# ETAPA_DE_POTENCIA.net
KiCad netlist of a schematic drawn in Altium Designer
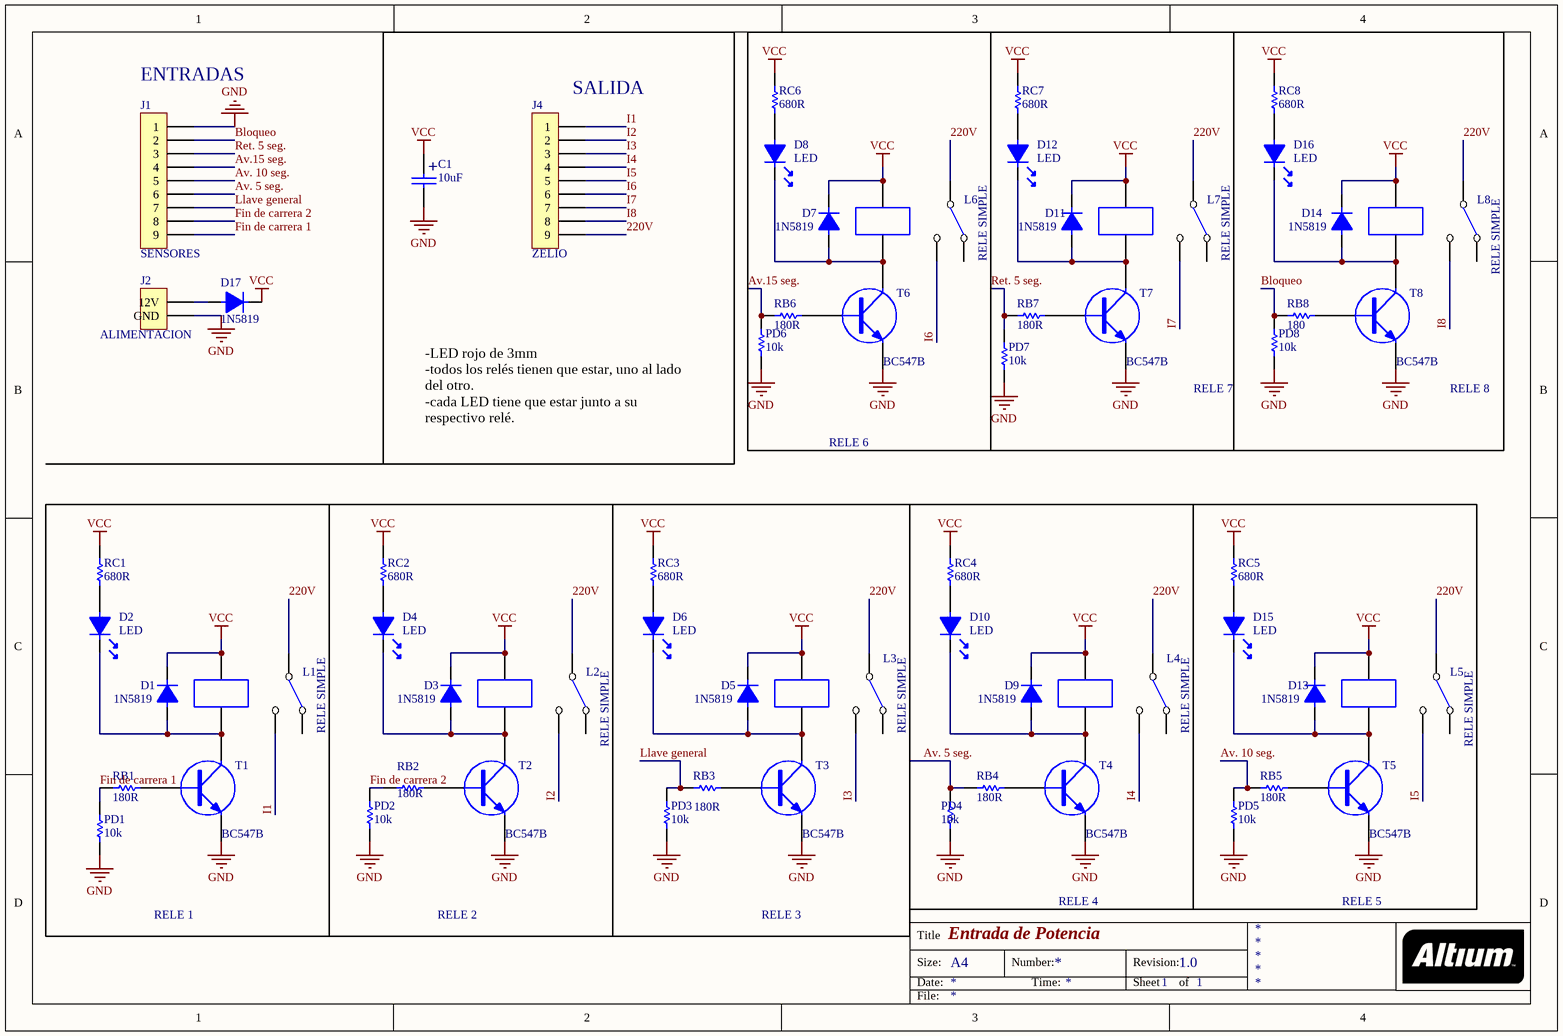
[diagram p0: ETAPA DE POTENCIA (1).SchDoc]

(export (version "E")
  (design (tool "Eeschema 10.0.6"))
  (components
    (comp (ref "C1") (value "10uF") (footprint "CAP100RP") (libsource (lib "LIBEBAL") (part "CAPPOL")))
    (comp (ref "D1") (value "1N5819") (footprint "DO41") (libsource (lib "LIBEBAL") (part "DIODO")))
    (comp (ref "D2") (value "LED") (footprint "LED3") (libsource (lib "LIBEBAL") (part "LED")))
    (comp (ref "D3") (value "1N5819") (footprint "DO41") (libsource (lib "LIBEBAL") (part "DIODO")))
    (comp (ref "D4") (value "LED") (footprint "LED3") (libsource (lib "LIBEBAL") (part "LED")))
    (comp (ref "D5") (value "1N5819") (footprint "DO41") (libsource (lib "LIBEBAL") (part "DIODO")))
    (comp (ref "D6") (value "LED") (footprint "LED3") (libsource (lib "LIBEBAL") (part "LED")))
    (comp (ref "D7") (value "1N5819") (footprint "DO41") (libsource (lib "LIBEBAL") (part "DIODO")))
    (comp (ref "D8") (value "LED") (footprint "LED3") (libsource (lib "LIBEBAL") (part "LED")))
    (comp (ref "D9") (value "1N5819") (footprint "DO41") (libsource (lib "LIBEBAL") (part "DIODO")))
    (comp (ref "D10") (value "LED") (footprint "LED3") (libsource (lib "LIBEBAL") (part "LED")))
    (comp (ref "D11") (value "1N5819") (footprint "DO41") (libsource (lib "LIBEBAL") (part "DIODO")))
    (comp (ref "D12") (value "LED") (footprint "LED3") (libsource (lib "LIBEBAL") (part "LED")))
    (comp (ref "D13") (value "1N5819") (footprint "DO41") (libsource (lib "LIBEBAL") (part "DIODO")))
    (comp (ref "D14") (value "1N5819") (footprint "DO41") (libsource (lib "LIBEBAL") (part "DIODO")))
    (comp (ref "D15") (value "LED") (footprint "LED3") (libsource (lib "LIBEBAL") (part "LED")))
    (comp (ref "D16") (value "LED") (footprint "LED3") (libsource (lib "LIBEBAL") (part "LED")))
    (comp (ref "D17") (value "1N5819") (footprint "DO41") (libsource (lib "LIBPIOIX 0314A") (part "DIODO")))
    (comp (ref "J1") (value "SENSORES") (footprint "BORNERA9") (libsource (lib "LIBEBAL") (part "BORNERA 9")))
    (comp (ref "J2")
      (value "ALIMENTACION")
      (footprint "BORNERA2")
      (libsource (lib "LIBEBAL") (part "BORNERA 2"))
    )
    (comp (ref "J4") (value "ZELIO") (footprint "BORNERA9") (libsource (lib "LIBEBAL") (part "BORNERA 9")))
    (comp (ref "L1")
      (value "RELE SIMPLE")
      (footprint "RELE SERIE 964")
      (libsource (lib "LIBEBAL") (part "RELE SIMPLE"))
    )
    (comp (ref "L2")
      (value "RELE SIMPLE")
      (footprint "RELE SERIE 964")
      (libsource (lib "LIBEBAL") (part "RELE SIMPLE"))
    )
    (comp (ref "L3")
      (value "RELE SIMPLE")
      (footprint "RELE SERIE 964")
      (libsource (lib "LIBEBAL") (part "RELE SIMPLE"))
    )
    (comp (ref "L4")
      (value "RELE SIMPLE")
      (footprint "RELE SERIE 964")
      (libsource (lib "LIBEBAL") (part "RELE SIMPLE"))
    )
    (comp (ref "L5")
      (value "RELE SIMPLE")
      (footprint "RELE SERIE 964")
      (libsource (lib "LIBEBAL") (part "RELE SIMPLE"))
    )
    (comp (ref "L6")
      (value "RELE SIMPLE")
      (footprint "RELE SERIE 964")
      (libsource (lib "LIBEBAL") (part "RELE SIMPLE"))
    )
    (comp (ref "L7")
      (value "RELE SIMPLE")
      (footprint "RELE SERIE 964")
      (libsource (lib "LIBEBAL") (part "RELE SIMPLE"))
    )
    (comp (ref "L8")
      (value "RELE SIMPLE")
      (footprint "RELE SERIE 964")
      (libsource (lib "LIBEBAL") (part "RELE SIMPLE"))
    )
    (comp (ref "PD1") (value "10k") (footprint "RES400") (libsource (lib "LIBEBAL") (part "RES")))
    (comp (ref "PD2") (value "10k") (footprint "RES400") (libsource (lib "LIBEBAL") (part "RES")))
    (comp (ref "PD3") (value "10k") (footprint "RES400") (libsource (lib "LIBEBAL") (part "RES")))
    (comp (ref "PD4") (value "10k") (footprint "RES400") (libsource (lib "LIBEBAL") (part "RES")))
    (comp (ref "PD5") (value "10k") (footprint "RES400") (libsource (lib "LIBEBAL") (part "RES")))
    (comp (ref "PD6") (value "10k") (footprint "RES400") (libsource (lib "LIBEBAL") (part "RES")))
    (comp (ref "PD7") (value "10k") (footprint "RES400") (libsource (lib "LIBEBAL") (part "RES")))
    (comp (ref "PD8") (value "10k") (footprint "RES400") (libsource (lib "LIBEBAL") (part "RES")))
    (comp (ref "RB1") (value "180R") (footprint "RES400") (libsource (lib "LIBEBAL") (part "RES")))
    (comp (ref "RB2") (value "180R") (footprint "RES400") (libsource (lib "LIBEBAL") (part "RES")))
    (comp (ref "RB3") (value "180R") (footprint "RES400") (libsource (lib "LIBEBAL") (part "RES")))
    (comp (ref "RB4") (value "180R") (footprint "RES400") (libsource (lib "LIBEBAL") (part "RES")))
    (comp (ref "RB5") (value "180R") (footprint "RES400") (libsource (lib "LIBEBAL") (part "RES")))
    (comp (ref "RB6") (value "180R") (footprint "RES400") (libsource (lib "LIBEBAL") (part "RES")))
    (comp (ref "RB7") (value "180R") (footprint "RES400") (libsource (lib "LIBEBAL") (part "RES")))
    (comp (ref "RB8") (value "180") (footprint "RES400") (libsource (lib "LIBEBAL") (part "RES")))
    (comp (ref "RC1") (value "680R") (footprint "RES400") (libsource (lib "LIBEBAL") (part "RES")))
    (comp (ref "RC2") (value "680R") (footprint "RES400") (libsource (lib "LIBEBAL") (part "RES")))
    (comp (ref "RC3") (value "680R") (footprint "RES400") (libsource (lib "LIBEBAL") (part "RES")))
    (comp (ref "RC4") (value "680R") (footprint "RES400") (libsource (lib "LIBEBAL") (part "RES")))
    (comp (ref "RC5") (value "680R") (footprint "RES400") (libsource (lib "LIBEBAL") (part "RES")))
    (comp (ref "RC6") (value "680R") (footprint "RES400") (libsource (lib "LIBEBAL") (part "RES")))
    (comp (ref "RC7") (value "680R") (footprint "RES400") (libsource (lib "LIBEBAL") (part "RES")))
    (comp (ref "RC8") (value "680R") (footprint "RES400") (libsource (lib "LIBEBAL") (part "RES")))
    (comp (ref "T1") (value "BC547B") (footprint "TO92") (libsource (lib "LIBEBAL") (part "TRANSISTOR NPN")))
    (comp (ref "T2") (value "BC547B") (footprint "TO92") (libsource (lib "LIBEBAL") (part "TRANSISTOR NPN")))
    (comp (ref "T3") (value "BC547B") (footprint "TO92") (libsource (lib "LIBEBAL") (part "TRANSISTOR NPN")))
    (comp (ref "T4") (value "BC547B") (footprint "TO92") (libsource (lib "LIBEBAL") (part "TRANSISTOR NPN")))
    (comp (ref "T5") (value "BC547B") (footprint "TO92") (libsource (lib "LIBEBAL") (part "TRANSISTOR NPN")))
    (comp (ref "T6") (value "BC547B") (footprint "TO92") (libsource (lib "LIBEBAL") (part "TRANSISTOR NPN")))
    (comp (ref "T7") (value "BC547B") (footprint "TO92") (libsource (lib "LIBEBAL") (part "TRANSISTOR NPN")))
    (comp (ref "T8") (value "BC547B") (footprint "TO92") (libsource (lib "LIBEBAL") (part "TRANSISTOR NPN")))
  )
  (nets
    (net (code "1") (name "/220V") (class "Default")
      (node (ref "J4") (pin "9") (pinfunction "9_9") (pintype "passive"))
      (node (ref "L1") (pin "C1") (pinfunction "C1_C1") (pintype "passive"))
      (node (ref "L2") (pin "C1") (pinfunction "C1_C1") (pintype "passive"))
      (node (ref "L3") (pin "C1") (pinfunction "C1_C1") (pintype "passive"))
      (node (ref "L4") (pin "C1") (pinfunction "C1_C1") (pintype "passive"))
      (node (ref "L5") (pin "C1") (pinfunction "C1_C1") (pintype "passive"))
      (node (ref "L6") (pin "C1") (pinfunction "C1_C1") (pintype "passive"))
      (node (ref "L7") (pin "C1") (pinfunction "C1_C1") (pintype "passive"))
      (node (ref "L8") (pin "C1") (pinfunction "C1_C1") (pintype "passive"))
    )
    (net (code "3") (name "/Av. 5 seg.") (class "Default")
      (node (ref "J1") (pin "6") (pinfunction "6_6") (pintype "passive"))
      (node (ref "PD4") (pin "2") (pinfunction "2_2") (pintype "passive"))
      (node (ref "RB4") (pin "1") (pinfunction "1_1") (pintype "passive"))
    )
    (net (code "4") (name "/Av. 10 seg.") (class "Default")
      (node (ref "J1") (pin "5") (pinfunction "5_5") (pintype "passive"))
      (node (ref "PD5") (pin "2") (pinfunction "2_2") (pintype "passive"))
      (node (ref "RB5") (pin "1") (pinfunction "1_1") (pintype "passive"))
    )
    (net (code "5") (name "/Av.15 seg.") (class "Default")
      (node (ref "J1") (pin "4") (pinfunction "4_4") (pintype "passive"))
      (node (ref "PD6") (pin "2") (pinfunction "2_2") (pintype "passive"))
      (node (ref "RB6") (pin "1") (pinfunction "1_1") (pintype "passive"))
    )
    (net (code "6") (name "/Bloqueo") (class "Default")
      (node (ref "J1") (pin "2") (pinfunction "2_2") (pintype "passive"))
      (node (ref "PD8") (pin "2") (pinfunction "2_2") (pintype "passive"))
      (node (ref "RB8") (pin "1") (pinfunction "1_1") (pintype "passive"))
    )
    (net (code "7") (name "/Fin de carrera 1") (class "Default")
      (node (ref "J1") (pin "9") (pinfunction "9_9") (pintype "passive"))
      (node (ref "PD1") (pin "2") (pinfunction "2_2") (pintype "passive"))
      (node (ref "RB1") (pin "1") (pinfunction "1_1") (pintype "passive"))
    )
    (net (code "8") (name "/Fin de carrera 2") (class "Default")
      (node (ref "J1") (pin "8") (pinfunction "8_8") (pintype "passive"))
      (node (ref "PD2") (pin "2") (pinfunction "2_2") (pintype "passive"))
      (node (ref "RB2") (pin "1") (pinfunction "1_1") (pintype "passive"))
    )
    (net (code "9") (name "/I1") (class "Default")
      (node (ref "J4") (pin "1") (pinfunction "1_1") (pintype "passive"))
      (node (ref "L1") (pin "NA1") (pinfunction "NA1_NA1") (pintype "passive"))
    )
    (net (code "10") (name "/I2") (class "Default")
      (node (ref "J4") (pin "2") (pinfunction "2_2") (pintype "passive"))
      (node (ref "L2") (pin "NA1") (pinfunction "NA1_NA1") (pintype "passive"))
    )
    (net (code "11") (name "/I3") (class "Default")
      (node (ref "J4") (pin "3") (pinfunction "3_3") (pintype "passive"))
      (node (ref "L3") (pin "NA1") (pinfunction "NA1_NA1") (pintype "passive"))
    )
    (net (code "12") (name "/I4") (class "Default")
      (node (ref "J4") (pin "4") (pinfunction "4_4") (pintype "passive"))
      (node (ref "L4") (pin "NA1") (pinfunction "NA1_NA1") (pintype "passive"))
    )
    (net (code "13") (name "/I5") (class "Default")
      (node (ref "J4") (pin "5") (pinfunction "5_5") (pintype "passive"))
      (node (ref "L5") (pin "NA1") (pinfunction "NA1_NA1") (pintype "passive"))
    )
    (net (code "14") (name "/I6") (class "Default")
      (node (ref "J4") (pin "6") (pinfunction "6_6") (pintype "passive"))
      (node (ref "L6") (pin "NA1") (pinfunction "NA1_NA1") (pintype "passive"))
    )
    (net (code "15") (name "/I7") (class "Default")
      (node (ref "J4") (pin "7") (pinfunction "7_7") (pintype "passive"))
      (node (ref "L7") (pin "NA1") (pinfunction "NA1_NA1") (pintype "passive"))
    )
    (net (code "16") (name "/I8") (class "Default")
      (node (ref "J4") (pin "8") (pinfunction "8_8") (pintype "passive"))
      (node (ref "L8") (pin "NA1") (pinfunction "NA1_NA1") (pintype "passive"))
    )
    (net (code "17") (name "/Llave general") (class "Default")
      (node (ref "J1") (pin "7") (pinfunction "7_7") (pintype "passive"))
      (node (ref "PD3") (pin "2") (pinfunction "2_2") (pintype "passive"))
      (node (ref "RB3") (pin "1") (pinfunction "1_1") (pintype "passive"))
    )
    (net (code "18") (name "/Ret. 5 seg.") (class "Default")
      (node (ref "J1") (pin "3") (pinfunction "3_3") (pintype "passive"))
      (node (ref "PD7") (pin "2") (pinfunction "2_2") (pintype "passive"))
      (node (ref "RB7") (pin "1") (pinfunction "1_1") (pintype "passive"))
    )
    (net (code "19") (name "GND") (class "Default")
      (node (ref "C1") (pin "2") (pinfunction "2_2") (pintype "passive"))
      (node (ref "J1") (pin "1") (pinfunction "1_1") (pintype "passive"))
      (node (ref "J2") (pin "2") (pinfunction "GND_2") (pintype "passive"))
      (node (ref "PD1") (pin "1") (pinfunction "1_1") (pintype "passive"))
      (node (ref "PD2") (pin "1") (pinfunction "1_1") (pintype "passive"))
      (node (ref "PD3") (pin "1") (pinfunction "1_1") (pintype "passive"))
      (node (ref "PD4") (pin "1") (pinfunction "1_1") (pintype "passive"))
      (node (ref "PD5") (pin "1") (pinfunction "1_1") (pintype "passive"))
      (node (ref "PD6") (pin "1") (pinfunction "1_1") (pintype "passive"))
      (node (ref "PD7") (pin "1") (pinfunction "1_1") (pintype "passive"))
      (node (ref "PD8") (pin "1") (pinfunction "1_1") (pintype "passive"))
      (node (ref "T1") (pin "3") (pinfunction "E_3") (pintype "passive"))
      (node (ref "T2") (pin "3") (pinfunction "E_3") (pintype "passive"))
      (node (ref "T3") (pin "3") (pinfunction "E_3") (pintype "passive"))
      (node (ref "T4") (pin "3") (pinfunction "E_3") (pintype "passive"))
      (node (ref "T5") (pin "3") (pinfunction "E_3") (pintype "passive"))
      (node (ref "T6") (pin "3") (pinfunction "E_3") (pintype "passive"))
      (node (ref "T7") (pin "3") (pinfunction "E_3") (pintype "passive"))
      (node (ref "T8") (pin "3") (pinfunction "E_3") (pintype "passive"))
    )
    (net (code "20") (name "Net-(D2-Pad1)") (class "Default")
      (node (ref "D2") (pin "1") (pinfunction "1_1") (pintype "passive"))
      (node (ref "RC1") (pin "2") (pinfunction "2_2") (pintype "passive"))
    )
    (net (code "21") (name "Net-(D4-Pad1)") (class "Default")
      (node (ref "D4") (pin "1") (pinfunction "1_1") (pintype "passive"))
      (node (ref "RC2") (pin "2") (pinfunction "2_2") (pintype "passive"))
    )
    (net (code "22") (name "Net-(D6-Pad1)") (class "Default")
      (node (ref "D6") (pin "1") (pinfunction "1_1") (pintype "passive"))
      (node (ref "RC3") (pin "2") (pinfunction "2_2") (pintype "passive"))
    )
    (net (code "23") (name "Net-(D8-Pad1)") (class "Default")
      (node (ref "D8") (pin "1") (pinfunction "1_1") (pintype "passive"))
      (node (ref "RC6") (pin "2") (pinfunction "2_2") (pintype "passive"))
    )
    (net (code "24") (name "Net-(D10-Pad1)") (class "Default")
      (node (ref "D10") (pin "1") (pinfunction "1_1") (pintype "passive"))
      (node (ref "RC4") (pin "2") (pinfunction "2_2") (pintype "passive"))
    )
    (net (code "25") (name "Net-(D12-Pad1)") (class "Default")
      (node (ref "D12") (pin "1") (pinfunction "1_1") (pintype "passive"))
      (node (ref "RC7") (pin "2") (pinfunction "2_2") (pintype "passive"))
    )
    (net (code "26") (name "Net-(D15-Pad1)") (class "Default")
      (node (ref "D15") (pin "1") (pinfunction "1_1") (pintype "passive"))
      (node (ref "RC5") (pin "2") (pinfunction "2_2") (pintype "passive"))
    )
    (net (code "27") (name "Net-(D16-Pad1)") (class "Default")
      (node (ref "D16") (pin "1") (pinfunction "1_1") (pintype "passive"))
      (node (ref "RC8") (pin "2") (pinfunction "2_2") (pintype "passive"))
    )
    (net (code "28") (name "Net-(J2-12V)") (class "Default")
      (node (ref "D17") (pin "1") (pinfunction "1_1") (pintype "passive"))
      (node (ref "J2") (pin "1") (pinfunction "12V_1") (pintype "passive"))
    )
    (net (code "29") (name "Net-(T1-B)") (class "Default")
      (node (ref "RB1") (pin "2") (pinfunction "2_2") (pintype "passive"))
      (node (ref "T1") (pin "1") (pinfunction "B_1") (pintype "passive"))
    )
    (net (code "30") (name "Net-(T1-C)") (class "Default")
      (node (ref "D1") (pin "1") (pinfunction "1_1") (pintype "passive"))
      (node (ref "D2") (pin "2") (pinfunction "2_2") (pintype "passive"))
      (node (ref "L1") (pin "B1") (pinfunction "B1_B1") (pintype "passive"))
      (node (ref "T1") (pin "2") (pinfunction "C_2") (pintype "passive"))
    )
    (net (code "31") (name "Net-(T2-B)") (class "Default")
      (node (ref "RB2") (pin "2") (pinfunction "2_2") (pintype "passive"))
      (node (ref "T2") (pin "1") (pinfunction "B_1") (pintype "passive"))
    )
    (net (code "32") (name "Net-(T2-C)") (class "Default")
      (node (ref "D3") (pin "1") (pinfunction "1_1") (pintype "passive"))
      (node (ref "D4") (pin "2") (pinfunction "2_2") (pintype "passive"))
      (node (ref "L2") (pin "B1") (pinfunction "B1_B1") (pintype "passive"))
      (node (ref "T2") (pin "2") (pinfunction "C_2") (pintype "passive"))
    )
    (net (code "33") (name "Net-(T3-B)") (class "Default")
      (node (ref "RB3") (pin "2") (pinfunction "2_2") (pintype "passive"))
      (node (ref "T3") (pin "1") (pinfunction "B_1") (pintype "passive"))
    )
    (net (code "34") (name "Net-(T3-C)") (class "Default")
      (node (ref "D5") (pin "1") (pinfunction "1_1") (pintype "passive"))
      (node (ref "D6") (pin "2") (pinfunction "2_2") (pintype "passive"))
      (node (ref "L3") (pin "B1") (pinfunction "B1_B1") (pintype "passive"))
      (node (ref "T3") (pin "2") (pinfunction "C_2") (pintype "passive"))
    )
    (net (code "35") (name "Net-(T4-B)") (class "Default")
      (node (ref "RB4") (pin "2") (pinfunction "2_2") (pintype "passive"))
      (node (ref "T4") (pin "1") (pinfunction "B_1") (pintype "passive"))
    )
    (net (code "36") (name "Net-(T4-C)") (class "Default")
      (node (ref "D10") (pin "2") (pinfunction "2_2") (pintype "passive"))
      (node (ref "D9") (pin "1") (pinfunction "1_1") (pintype "passive"))
      (node (ref "L4") (pin "B1") (pinfunction "B1_B1") (pintype "passive"))
      (node (ref "T4") (pin "2") (pinfunction "C_2") (pintype "passive"))
    )
    (net (code "37") (name "Net-(T5-B)") (class "Default")
      (node (ref "RB5") (pin "2") (pinfunction "2_2") (pintype "passive"))
      (node (ref "T5") (pin "1") (pinfunction "B_1") (pintype "passive"))
    )
    (net (code "38") (name "Net-(T5-C)") (class "Default")
      (node (ref "D13") (pin "1") (pinfunction "1_1") (pintype "passive"))
      (node (ref "D15") (pin "2") (pinfunction "2_2") (pintype "passive"))
      (node (ref "L5") (pin "B1") (pinfunction "B1_B1") (pintype "passive"))
      (node (ref "T5") (pin "2") (pinfunction "C_2") (pintype "passive"))
    )
    (net (code "39") (name "Net-(T6-B)") (class "Default")
      (node (ref "RB6") (pin "2") (pinfunction "2_2") (pintype "passive"))
      (node (ref "T6") (pin "1") (pinfunction "B_1") (pintype "passive"))
    )
    (net (code "40") (name "Net-(T6-C)") (class "Default")
      (node (ref "D7") (pin "1") (pinfunction "1_1") (pintype "passive"))
      (node (ref "D8") (pin "2") (pinfunction "2_2") (pintype "passive"))
      (node (ref "L6") (pin "B1") (pinfunction "B1_B1") (pintype "passive"))
      (node (ref "T6") (pin "2") (pinfunction "C_2") (pintype "passive"))
    )
    (net (code "41") (name "Net-(T7-B)") (class "Default")
      (node (ref "RB7") (pin "2") (pinfunction "2_2") (pintype "passive"))
      (node (ref "T7") (pin "1") (pinfunction "B_1") (pintype "passive"))
    )
    (net (code "42") (name "Net-(T7-C)") (class "Default")
      (node (ref "D11") (pin "1") (pinfunction "1_1") (pintype "passive"))
      (node (ref "D12") (pin "2") (pinfunction "2_2") (pintype "passive"))
      (node (ref "L7") (pin "B1") (pinfunction "B1_B1") (pintype "passive"))
      (node (ref "T7") (pin "2") (pinfunction "C_2") (pintype "passive"))
    )
    (net (code "43") (name "Net-(T8-B)") (class "Default")
      (node (ref "RB8") (pin "2") (pinfunction "2_2") (pintype "passive"))
      (node (ref "T8") (pin "1") (pinfunction "B_1") (pintype "passive"))
    )
    (net (code "44") (name "Net-(T8-C)") (class "Default")
      (node (ref "D14") (pin "1") (pinfunction "1_1") (pintype "passive"))
      (node (ref "D16") (pin "2") (pinfunction "2_2") (pintype "passive"))
      (node (ref "L8") (pin "B1") (pinfunction "B1_B1") (pintype "passive"))
      (node (ref "T8") (pin "2") (pinfunction "C_2") (pintype "passive"))
    )
    (net (code "45") (name "VCC") (class "Default")
      (node (ref "C1") (pin "1") (pinfunction "1_1") (pintype "passive"))
      (node (ref "D1") (pin "2") (pinfunction "2_2") (pintype "passive"))
      (node (ref "D11") (pin "2") (pinfunction "2_2") (pintype "passive"))
      (node (ref "D13") (pin "2") (pinfunction "2_2") (pintype "passive"))
      (node (ref "D14") (pin "2") (pinfunction "2_2") (pintype "passive"))
      (node (ref "D17") (pin "2") (pinfunction "2_2") (pintype "passive"))
      (node (ref "D3") (pin "2") (pinfunction "2_2") (pintype "passive"))
      (node (ref "D5") (pin "2") (pinfunction "2_2") (pintype "passive"))
      (node (ref "D7") (pin "2") (pinfunction "2_2") (pintype "passive"))
      (node (ref "D9") (pin "2") (pinfunction "2_2") (pintype "passive"))
      (node (ref "L1") (pin "B2") (pinfunction "B2_B2") (pintype "passive"))
      (node (ref "L2") (pin "B2") (pinfunction "B2_B2") (pintype "passive"))
      (node (ref "L3") (pin "B2") (pinfunction "B2_B2") (pintype "passive"))
      (node (ref "L4") (pin "B2") (pinfunction "B2_B2") (pintype "passive"))
      (node (ref "L5") (pin "B2") (pinfunction "B2_B2") (pintype "passive"))
      (node (ref "L6") (pin "B2") (pinfunction "B2_B2") (pintype "passive"))
      (node (ref "L7") (pin "B2") (pinfunction "B2_B2") (pintype "passive"))
      (node (ref "L8") (pin "B2") (pinfunction "B2_B2") (pintype "passive"))
      (node (ref "RC1") (pin "1") (pinfunction "1_1") (pintype "passive"))
      (node (ref "RC2") (pin "1") (pinfunction "1_1") (pintype "passive"))
      (node (ref "RC3") (pin "1") (pinfunction "1_1") (pintype "passive"))
      (node (ref "RC4") (pin "1") (pinfunction "1_1") (pintype "passive"))
      (node (ref "RC5") (pin "1") (pinfunction "1_1") (pintype "passive"))
      (node (ref "RC6") (pin "1") (pinfunction "1_1") (pintype "passive"))
      (node (ref "RC7") (pin "1") (pinfunction "1_1") (pintype "passive"))
      (node (ref "RC8") (pin "1") (pinfunction "1_1") (pintype "passive"))
    )
    (net (code "46") (name "unconnected-(L1-PadNC1)") (class "Default")
      (node (ref "L1") (pin "NC1") (pinfunction "NC1_NC1") (pintype "passive"))
    )
    (net (code "47") (name "unconnected-(L2-PadNC1)") (class "Default")
      (node (ref "L2") (pin "NC1") (pinfunction "NC1_NC1") (pintype "passive"))
    )
    (net (code "48") (name "unconnected-(L3-PadNC1)") (class "Default")
      (node (ref "L3") (pin "NC1") (pinfunction "NC1_NC1") (pintype "passive"))
    )
    (net (code "49") (name "unconnected-(L4-PadNC1)") (class "Default")
      (node (ref "L4") (pin "NC1") (pinfunction "NC1_NC1") (pintype "passive"))
    )
    (net (code "50") (name "unconnected-(L5-PadNC1)") (class "Default")
      (node (ref "L5") (pin "NC1") (pinfunction "NC1_NC1") (pintype "passive"))
    )
    (net (code "51") (name "unconnected-(L6-PadNC1)") (class "Default")
      (node (ref "L6") (pin "NC1") (pinfunction "NC1_NC1") (pintype "passive"))
    )
    (net (code "52") (name "unconnected-(L7-PadNC1)") (class "Default")
      (node (ref "L7") (pin "NC1") (pinfunction "NC1_NC1") (pintype "passive"))
    )
    (net (code "53") (name "unconnected-(L8-PadNC1)") (class "Default")
      (node (ref "L8") (pin "NC1") (pinfunction "NC1_NC1") (pintype "passive"))
    )
  )
)
